# MB1-SD_CARD.net
KiCad netlist of a schematic drawn in Altium Designer
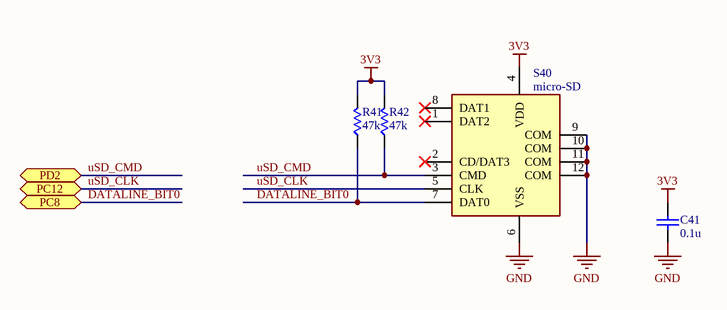
[diagram p0: MB1-SD_CARD.SchDoc]

(export (version "E")
  (design (tool "Eeschema 10.0.6"))
  (components
    (comp (ref "C41")
      (value "0.1u")
      (footprint "SM_0805_LD")
      (description "Non-polarity ceramic capacitor")
      (fields (field (name "Comment") "CAP_Ceramic") (field (name "PUBLISHER") "Altium Limited"))
      (libsource (lib "Copy of HLib_device_library") (part "C_Ceramic"))
    )
    (comp (ref "R41")
      (value "47k")
      (footprint "SM_0805_LD")
      (description "Resistor")
      (fields (field (name "PUBLISHER") "Altium Limited"))
      (libsource (lib "Copy of HLib_device_library") (part "R"))
    )
    (comp (ref "R42")
      (value "47k")
      (footprint "SM_0805_LD")
      (description "Resistor")
      (fields (field (name "PUBLISHER") "Altium Limited"))
      (libsource (lib "Copy of HLib_device_library") (part "R"))
    )
    (comp (ref "S40") (value "micro-SD") (footprint "micro-SD") (libsource (lib "MyLib") (part "micro-SD")))
  )
  (nets
    (net (code "1") (name "/DATALINE_BIT0") (class "Default")
      (node (ref "R41") (pin "1") (pinfunction "1_1") (pintype "passive"))
      (node (ref "S40") (pin "7") (pinfunction "DAT0_7") (pintype "passive"))
    )
    (net (code "2") (name "/uSD_CLK") (class "Default")
      (node (ref "S40") (pin "5") (pinfunction "CLK_5") (pintype "passive"))
    )
    (net (code "3") (name "/uSD_CMD") (class "Default")
      (node (ref "R42") (pin "1") (pinfunction "1_1") (pintype "passive"))
      (node (ref "S40") (pin "3") (pinfunction "CMD_3") (pintype "passive"))
    )
    (net (code "4") (name "3V3") (class "Default")
      (node (ref "C41") (pin "2") (pinfunction "2_2") (pintype "passive"))
      (node (ref "R41") (pin "2") (pinfunction "2_2") (pintype "passive"))
      (node (ref "R42") (pin "2") (pinfunction "2_2") (pintype "passive"))
      (node (ref "S40") (pin "4") (pinfunction "VDD_4") (pintype "passive"))
    )
    (net (code "5") (name "GND") (class "Default")
      (node (ref "C41") (pin "1") (pinfunction "1_1") (pintype "passive"))
      (node (ref "S40") (pin "10") (pinfunction "COM_10") (pintype "passive"))
      (node (ref "S40") (pin "11") (pinfunction "COM_11") (pintype "passive"))
      (node (ref "S40") (pin "12") (pinfunction "COM_12") (pintype "passive"))
      (node (ref "S40") (pin "6") (pinfunction "VSS_6") (pintype "passive"))
      (node (ref "S40") (pin "9") (pinfunction "COM_9") (pintype "passive"))
    )
    (net (code "6") (name "unconnected-(S40-CD{slash}DAT3-Pad2)") (class "Default")
      (node (ref "S40") (pin "2") (pinfunction "CD/DAT3_2") (pintype "passive+no_connect"))
    )
    (net (code "7") (name "unconnected-(S40-DAT1-Pad8)") (class "Default")
      (node (ref "S40") (pin "8") (pinfunction "DAT1_8") (pintype "passive+no_connect"))
    )
    (net (code "8") (name "unconnected-(S40-DAT2-Pad1)") (class "Default")
      (node (ref "S40") (pin "1") (pinfunction "DAT2_1") (pintype "passive+no_connect"))
    )
  )
)
